# Flyback_Converter.net
KiCad netlist of a schematic drawn in Altium Designer
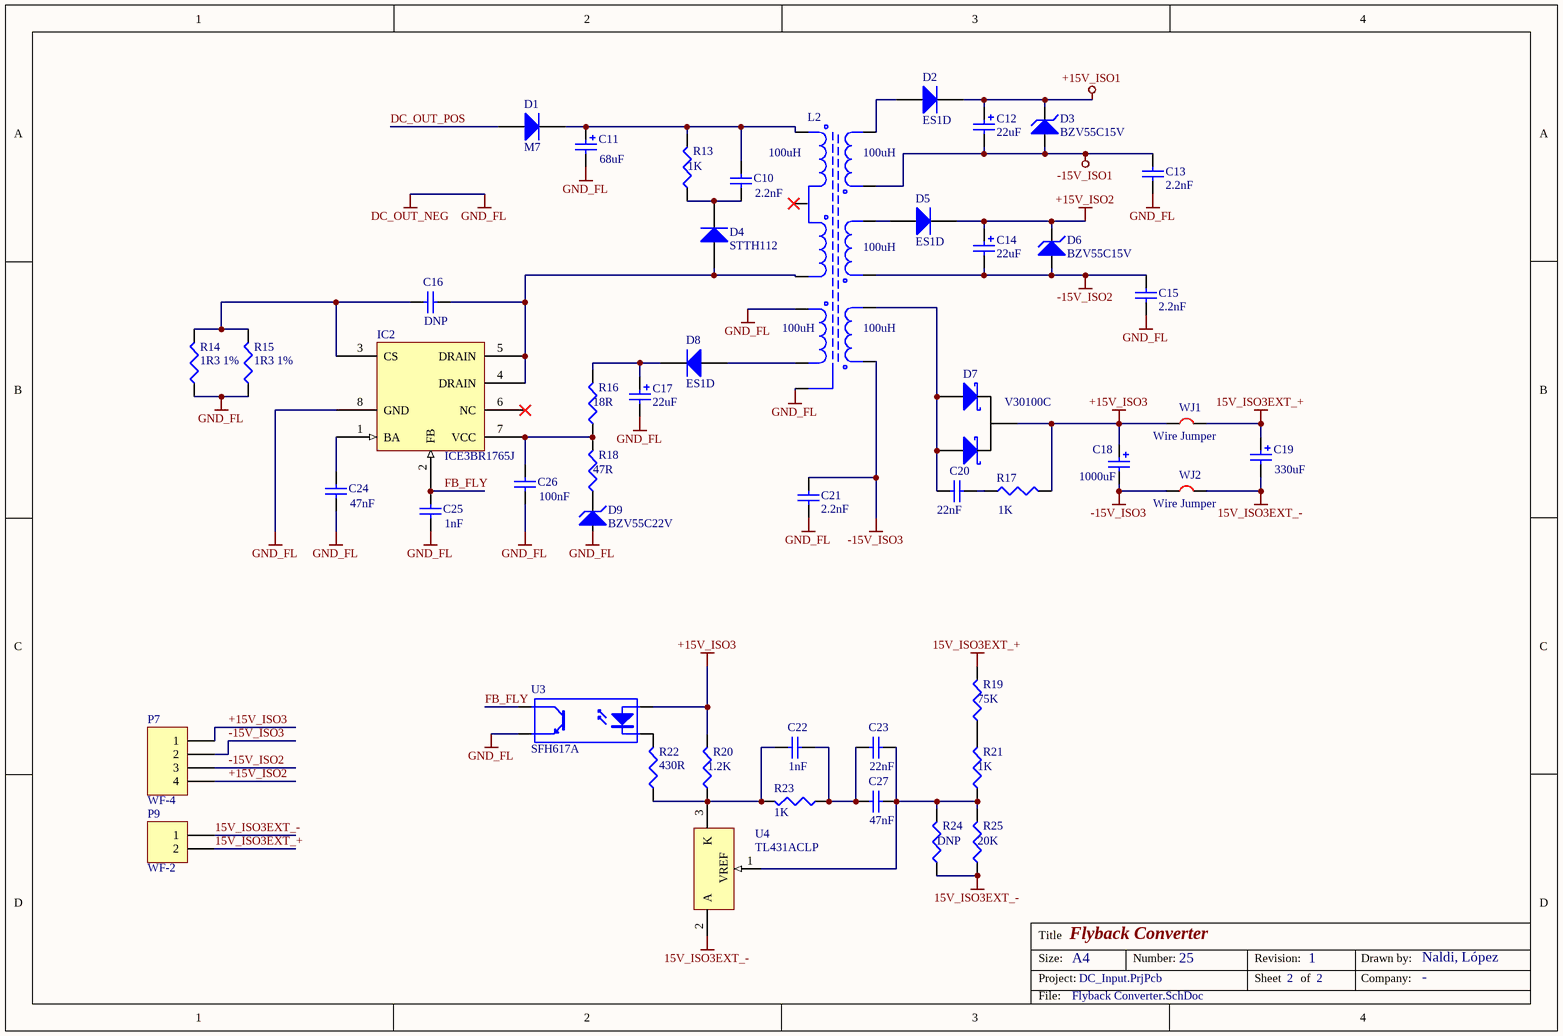
[diagram p0: Flyback Converter.SchDoc]

(export (version "E")
  (design (tool "Eeschema 10.0.6"))
  (components
    (comp (ref "C10")
      (value "2.2nF")
      (footprint "CAPC3216X18N 1206")
      (description "Ceramic Multilayer 2.2nF 630Vdc COG")
      (fields (field (name "Comment") "TDK C3216C0G2J222J115AA") (field (name "PUBLISHER") "Altium Limited"))
      (libsource (lib "Capacitor") (part "TDK C3216C0G2J222J115AA"))
    )
    (comp (ref "C11")
      (value "68uF")
      (footprint "Radial, pitch: 7.5mm diam:18mm")
      (description "MINIATURE ALUMINUM ELECTROLYTIC 68uF 400V 105ºC")
      (fields
        (field (name "Comment") "RUBYCON 400BXC68MEFC18X25")
        (field (name "PUBLISHER") "Altium Limited")
      )
      (libsource (lib "Capacitor") (part "RUBYCON 400BXC68MEFC18X25"))
    )
    (comp (ref "C12")
      (value "22uF")
      (footprint "Radial, Pitch: 2mm Diam: 5mm")
      (description "ALUMINUM ELECTROLYTIC 22UFX50V")
      (fields (field (name "Comment") "EPCOS B41827A6226M000") (field (name "PUBLISHER") "Altium Limited"))
      (libsource (lib "Capacitor") (part "EPCOS B41827A6226M000"))
    )
    (comp (ref "C13")
      (value "2.2nF")
      (footprint "SAFETY Y1 type")
      (description "Safety Standard Certified Ceramic Y1 2.2nF 250Vac")
      (fields (field (name "Comment") "TDK CD12-E2GA222MYNS") (field (name "PUBLISHER") "Altium Limited"))
      (libsource (lib "Capacitor") (part "TDK CD12-E2GA222MYNS"))
    )
    (comp (ref "C14")
      (value "22uF")
      (footprint "Radial, Pitch: 2mm Diam: 5mm")
      (description "ALUMINUM ELECTROLYTIC 22UFX50V")
      (fields (field (name "Comment") "EPCOS B41827A6226M000") (field (name "PUBLISHER") "Altium Limited"))
      (libsource (lib "Capacitor") (part "EPCOS B41827A6226M000"))
    )
    (comp (ref "C15")
      (value "2.2nF")
      (footprint "Chip2PinSM127P600-8N_safety")
      (description "Safety Standard Certified Ceramic Y2 2.2nF 250Vac")
      (fields
        (field (name "Comment") "MURATA GA355QR7GF222KW01L")
        (field (name "PUBLISHER") "Altium Limited")
      )
      (libsource (lib "Capacitor") (part "MURATA GA355QR7GF222KW01L"))
    )
    (comp (ref "C16")
      (value "DNP")
      (footprint "CAPC3216X18N 1206")
      (description "Ceramic Multilayer  50Vdc C0G")
      (fields (field (name "Comment") "EPCOS B37871K5221J60") (field (name "PUBLISHER") "Altium Limited"))
      (libsource (lib "Capacitor") (part "EPCOS B37871K5221J60"))
    )
    (comp (ref "C17")
      (value "22uF")
      (footprint "Radial, Pitch: 2mm Diam: 5mm")
      (description "ALUMINUM ELECTROLYTIC 22UFX50V")
      (fields (field (name "Comment") "EPCOS B41827A6226M000") (field (name "PUBLISHER") "Altium Limited"))
      (libsource (lib "Capacitor") (part "EPCOS B41827A6226M000"))
    )
    (comp (ref "C18")
      (value "1000uF")
      (footprint "Rad 12.5mm  pitch: 5mm")
      (description "ALuminum Electrolytic Low Impedance 105 °C 1000uF x 25V")
      (fields (field (name "Comment") "EPCOS B41856A5108M000") (field (name "PUBLISHER") "Altium Limited"))
      (libsource (lib "Capacitor") (part "EPCOS B41856A5108M000"))
    )
    (comp (ref "C19")
      (value "330uF")
      (footprint "Rad 10mm  pitch: 5mm")
      (description "ALuminum Electrolytic Low Impedance 105 °C 330uF x 25V")
      (fields (field (name "Comment") "EPCOS B41856A5337M008") (field (name "PUBLISHER") "Altium Limited"))
      (libsource (lib "Capacitor") (part "EPCOS B41856A5337M008"))
    )
    (comp (ref "C20")
      (value "22nF")
      (footprint "CAPC3216X18N 1206")
      (description "Ceramic Multilayer 22nF 50Vdc X7R")
      (fields (field (name "Comment") "EPCOS B37872K5223K60") (field (name "PUBLISHER") "Altium Limited"))
      (libsource (lib "Capacitor") (part "EPCOS B37872K5223K60"))
    )
    (comp (ref "C21")
      (value "2.2nF")
      (footprint "SAFETY Y1 type")
      (description "Safety Standard Certified Ceramic Y1 2.2nF 250Vac")
      (fields (field (name "Comment") "TDK CD12-E2GA222MYNS") (field (name "PUBLISHER") "Altium Limited"))
      (libsource (lib "Capacitor") (part "TDK CD12-E2GA222MYNS"))
    )
    (comp (ref "C22")
      (value "1nF")
      (footprint "Chip2PinSM127P600-8N")
      (description "Ceramic Multilayer 1nF 50Vdc COG")
      (fields (field (name "Comment") "EPCOS B37940K51102J60") (field (name "PUBLISHER") "Altium Limited"))
      (libsource (lib "Capacitor") (part "EPCOS B37940K51102J60"))
    )
    (comp (ref "C23")
      (value "22nF")
      (footprint "CAPC3216X18N 1206")
      (description "Ceramic Multilayer 22nF 50Vdc X7R")
      (fields (field (name "Comment") "EPCOS B37872K5223K60") (field (name "PUBLISHER") "Altium Limited"))
      (libsource (lib "Capacitor") (part "EPCOS B37872K5223K60"))
    )
    (comp (ref "C24")
      (value "47nF")
      (footprint "CAPC3216X18N 1206")
      (description "Ceramic Multilayer 47nF 50Vdc X7R")
      (fields (field (name "Comment") "EPCOS CL31B473KBCNNNC") (field (name "PUBLISHER") "Altium Limited"))
      (libsource (lib "Capacitor") (part "EPCOS CL31B473KBCNNNC"))
    )
    (comp (ref "C25")
      (value "1nF")
      (footprint "MKT Pitch: 5mm 2.5 × 7.3 mm")
      (description "MKT General purpose 1nF 63Vdc")
      (fields (field (name "Comment") "EPCOS B32529C0102K000") (field (name "PUBLISHER") "Altium Limited"))
      (libsource (lib "Capacitor") (part "EPCOS B32529C0102K000"))
    )
    (comp (ref "C26")
      (value "100nF")
      (footprint "Chip2PinSM127P600-8N")
      (description "Ceramic Multilayer 100nF 50Vdc X7R")
      (fields (field (name "Comment") "EPCOS C2012X7R1H104K") (field (name "PUBLISHER") "Altium Limited"))
      (libsource (lib "Capacitor") (part "EPCOS C2012X7R1H104K"))
    )
    (comp (ref "C27")
      (value "47nF")
      (footprint "CAPC3216X18N 1206")
      (description "Ceramic Multilayer 47nF 50Vdc X7R")
      (fields (field (name "Comment") "EPCOS CL31B473KBCNNNC") (field (name "PUBLISHER") "Altium Limited"))
      (libsource (lib "Capacitor") (part "EPCOS CL31B473KBCNNNC"))
    )
    (comp (ref "D1")
      (value "M7")
      (footprint "DIOM4326X26N - SMA")
      (description "1A 1000V SMA")
      (fields (field (name "PUBLISHER") "Altium Limited"))
      (libsource (lib "Diode") (part "M7 SMA"))
    )
    (comp (ref "D2")
      (value "ES1D")
      (footprint "DIOM4326X26N - SMA")
      (description "Ultrafast rectifier 1A 200V")
      (fields (field (name "PUBLISHER") "Altium Limited"))
      (libsource (lib "Diode") (part "ES1D"))
    )
    (comp (ref "D3")
      (value "BZV55C15V")
      (footprint "DIOMELF3515N")
      (description "Zener Diode 15V 0.5W")
      (fields (field (name "PUBLISHER") "Altium Limited"))
      (libsource (lib "Diode") (part "BZV55C15V"))
    )
    (comp (ref "D4")
      (value "STTH112")
      (footprint "DIOM4336X26N - SMB")
      (description "High voltage ultrafast rectifier")
      (fields (field (name "PUBLISHER") "Altium Limited"))
      (libsource (lib "Diode") (part "STTH112"))
    )
    (comp (ref "D5")
      (value "ES1D")
      (footprint "DIOM4326X26N - SMA")
      (description "Ultrafast rectifier 1A 200V")
      (fields (field (name "PUBLISHER") "Altium Limited"))
      (libsource (lib "Diode") (part "ES1D"))
    )
    (comp (ref "D6")
      (value "BZV55C15V")
      (footprint "DIOMELF3515N")
      (description "Zener Diode 15V 0.5W")
      (fields (field (name "PUBLISHER") "Altium Limited"))
      (libsource (lib "Diode") (part "BZV55C15V"))
    )
    (comp (ref "D7")
      (value "V30100C")
      (footprint "TO-220 Horiz. Heatsink")
      (description "Trench MOS Barrier Schottky Rectifier 2x 15A 100V")
      (libsource (lib "Diode") (part "V30100C"))
    )
    (comp (ref "D8")
      (value "ES1D")
      (footprint "DIOM4326X26N - SMA")
      (description "Ultrafast rectifier 1A 200V")
      (fields (field (name "PUBLISHER") "Altium Limited"))
      (libsource (lib "Diode") (part "ES1D"))
    )
    (comp (ref "D9")
      (value "BZV55C22V")
      (footprint "DIOMELF3515N")
      (description "Zener Diode 22V 0.5W")
      (fields (field (name "PUBLISHER") "Altium Limited"))
      (libsource (lib "Diode") (part "BZV55C22V"))
    )
    (comp (ref "IC2")
      (value "ICE3BR1765J")
      (footprint "PDIP8")
      (libsource (lib "PWM Controller") (part "ICE3BR1765J"))
    )
    (comp (ref "L2")
      (value "2 Primary, 3 Secondary, Shield")
      (footprint "CORE_E_20/10/6_14pin")
      (description "Coupled Inductors with Ferrite Core")
      (fields
        (field (name "VALUE_P1") "100uH")
        (field (name "VALUE_P2") "100uH")
        (field (name "VALUE_S1") "100uH")
        (field (name "VALUE_S2") "100uH")
        (field (name "VALUE_S3") "100uH")
        (field (name "PUBLISHER") "Altium Limited")
      )
      (libsource (lib "Inductor") (part "2 Primary, 3 Secondary, Shield"))
    )
    (comp (ref "P7")
      (value "WF-4")
      (footprint "HDR1X4")
      (description "Header, 4-Pin, 2.54mm pitch")
      (fields (field (name "PUBLISHER") "Altium Limited"))
      (libsource (lib "Connector") (part "Header 4"))
    )
    (comp (ref "P9")
      (value "WF-2")
      (footprint "HDR1X2")
      (description "Header, 2-Pin, 2.54mm pitch")
      (fields (field (name "PUBLISHER") "Altium Limited"))
      (libsource (lib "Connector") (part "Header 2"))
    )
    (comp (ref "R13")
      (value "1K")
      (footprint "Chip2PinSM127P600-8N 2512")
      (description "Resistor SMD 2512 1W")
      (fields (field (name "Comment") "Resistor SMD 2512") (field (name "PUBLISHER") "Altium Limited"))
      (libsource (lib "Resistor") (part "Resistor SMD 2512"))
    )
    (comp (ref "R14")
      (value "1R3 1%")
      (footprint "RESC3116X07N - 1206")
      (description "Resistor SMD 1206")
      (fields (field (name "PUBLISHER") "Altium Limited"))
      (libsource (lib "Resistor") (part "Resistor SMD 1206"))
    )
    (comp (ref "R15")
      (value "1R3 1%")
      (footprint "RESC3116X07N - 1206")
      (description "Resistor SMD 1206")
      (fields (field (name "PUBLISHER") "Altium Limited"))
      (libsource (lib "Resistor") (part "Resistor SMD 1206"))
    )
    (comp (ref "R16")
      (value "18R")
      (footprint "Chip2PinSM127P600-8N - 0805")
      (description "Resistor SMD 0805")
      (fields (field (name "PUBLISHER") "Altium Limited"))
      (libsource (lib "Resistor") (part "Resistor SMD 0805"))
    )
    (comp (ref "R17")
      (value "1K")
      (footprint "RESC3116X07N - 1206")
      (description "Resistor SMD 1206")
      (fields (field (name "PUBLISHER") "Altium Limited"))
      (libsource (lib "Resistor") (part "Resistor SMD 1206"))
    )
    (comp (ref "R18")
      (value "47R")
      (footprint "Chip2PinSM127P600-8N - 0805")
      (description "Resistor SMD 0805")
      (fields (field (name "PUBLISHER") "Altium Limited"))
      (libsource (lib "Resistor") (part "Resistor SMD 0805"))
    )
    (comp (ref "R19")
      (value "75K")
      (footprint "AXIAL-0.3")
      (description "Resistor 1/4W 5%")
      (fields (field (name "Comment") "Resistor Through-hole") (field (name "PUBLISHER") "Altium Limited"))
      (libsource (lib "Resistor") (part "Resistor"))
    )
    (comp (ref "R20")
      (value "1.2K")
      (footprint "Chip2PinSM127P600-8N - 0805")
      (description "Resistor SMD 0805")
      (fields (field (name "PUBLISHER") "Altium Limited"))
      (libsource (lib "Resistor") (part "Resistor SMD 0805"))
    )
    (comp (ref "R21")
      (value "1K")
      (footprint "Chip2PinSM127P600-8N - 0805")
      (description "Resistor SMD 0805")
      (fields (field (name "PUBLISHER") "Altium Limited"))
      (libsource (lib "Resistor") (part "Resistor SMD 0805"))
    )
    (comp (ref "R22")
      (value "430R")
      (footprint "Chip2PinSM127P600-8N - 0805")
      (description "Resistor SMD 0805")
      (fields (field (name "PUBLISHER") "Altium Limited"))
      (libsource (lib "Resistor") (part "Resistor SMD 0805"))
    )
    (comp (ref "R23")
      (value "1K")
      (footprint "Chip2PinSM127P600-8N - 0805")
      (description "Resistor SMD 0805")
      (fields (field (name "PUBLISHER") "Altium Limited"))
      (libsource (lib "Resistor") (part "Resistor SMD 0805"))
    )
    (comp (ref "R24")
      (value "DNP")
      (footprint "Chip2PinSM127P600-8N - 0805")
      (description "Resistor SMD 0805")
      (fields (field (name "PUBLISHER") "Altium Limited"))
      (libsource (lib "Resistor") (part "Resistor SMD 0805"))
    )
    (comp (ref "R25")
      (value "20K")
      (footprint "Chip2PinSM127P600-8N - 0805")
      (description "Resistor SMD 0805")
      (fields (field (name "PUBLISHER") "Altium Limited"))
      (libsource (lib "Resistor") (part "Resistor SMD 0805"))
    )
    (comp (ref "U3")
      (value "SFH617A")
      (footprint "DIP4")
      (description "Phototransistor Output, High Reliability,  5300 VRMS, 110 °C Rated")
      (fields (field (name "PUBLISHER") "Altium Limited"))
      (libsource (lib "Optocoupler") (part "SFH617A"))
    )
    (comp (ref "U4")
      (value "TL431ACLP")
      (footprint "LP03")
      (description "Adjustable Precision Shunt Regulator")
      (fields (field (name "PUBLISHER") "Altium Limited"))
      (libsource (lib "TI Power Mgt Voltage Regulator") (part "TL431ACLP"))
    )
    (comp (ref "WJ1") (value "Wire Jumper") (libsource (lib "SamacSys") (part "Wire Jumper")))
    (comp (ref "WJ2") (value "Wire Jumper") (libsource (lib "SamacSys") (part "Wire Jumper")))
  )
  (nets
    (net (code "1") (name "+15V_ISO1") (class "Default")
      (node (ref "C12") (pin "1") (pinfunction "1_1") (pintype "passive"))
      (node (ref "D2") (pin "1") (pinfunction "K_1") (pintype "passive"))
      (node (ref "D3") (pin "2") (pinfunction "K_2") (pintype "passive"))
    )
    (net (code "2") (name "+15V_ISO2") (class "Default")
      (node (ref "C14") (pin "1") (pinfunction "1_1") (pintype "passive"))
      (node (ref "D5") (pin "1") (pinfunction "K_1") (pintype "passive"))
      (node (ref "D6") (pin "2") (pinfunction "K_2") (pintype "passive"))
      (node (ref "P7") (pin "4") (pinfunction "4_4") (pintype "passive"))
    )
    (net (code "3") (name "+15V_ISO3") (class "Default")
      (node (ref "C18") (pin "1") (pinfunction "1_1") (pintype "passive"))
      (node (ref "D7") (pin "2") (pinfunction "K12_2") (pintype "passive"))
      (node (ref "P7") (pin "1") (pinfunction "1_1") (pintype "passive"))
      (node (ref "R17") (pin "2") (pinfunction "2_2") (pintype "passive"))
      (node (ref "R20") (pin "2") (pinfunction "2_2") (pintype "passive"))
      (node (ref "U3") (pin "1") (pinfunction "A_1") (pintype "passive"))
      (node (ref "WJ1") (pin "0") (pinfunction "0_0") (pintype "passive"))
    )
    (net (code "4") (name "-15V_ISO1") (class "Default")
      (node (ref "C12") (pin "2") (pinfunction "2_2") (pintype "passive"))
      (node (ref "C13") (pin "2") (pinfunction "2_2") (pintype "passive"))
      (node (ref "D3") (pin "1") (pinfunction "A_1") (pintype "passive"))
      (node (ref "L2") (pin "9") (pinfunction "9_9") (pintype "passive"))
    )
    (net (code "5") (name "-15V_ISO2") (class "Default")
      (node (ref "C14") (pin "2") (pinfunction "2_2") (pintype "passive"))
      (node (ref "C15") (pin "1") (pinfunction "1_1") (pintype "passive"))
      (node (ref "D6") (pin "1") (pinfunction "A_1") (pintype "passive"))
      (node (ref "L2") (pin "11") (pinfunction "11_11") (pintype "passive"))
      (node (ref "P7") (pin "3") (pinfunction "3_3") (pintype "passive"))
    )
    (net (code "6") (name "-15V_ISO3") (class "Default")
      (node (ref "C18") (pin "2") (pinfunction "2_2") (pintype "passive"))
      (node (ref "C21") (pin "2") (pinfunction "2_2") (pintype "passive"))
      (node (ref "L2") (pin "13") (pinfunction "13_13") (pintype "passive"))
      (node (ref "P7") (pin "2") (pinfunction "2_2") (pintype "passive"))
      (node (ref "WJ2") (pin "0") (pinfunction "0_0") (pintype "passive"))
    )
    (net (code "7") (name "/DC_OUT_POS") (class "Default")
      (node (ref "D1") (pin "2") (pinfunction "A_2") (pintype "passive"))
    )
    (net (code "8") (name "/FB_FLY") (class "Default")
      (node (ref "C25") (pin "2") (pinfunction "2_2") (pintype "passive"))
      (node (ref "IC2") (pin "2") (pinfunction "FB_2") (pintype "input"))
      (node (ref "U3") (pin "4") (pinfunction "C_4") (pintype "passive"))
    )
    (net (code "9") (name "15V_ISO3EXT_+") (class "Default")
      (node (ref "C19") (pin "1") (pinfunction "1_1") (pintype "passive"))
      (node (ref "P9") (pin "2") (pinfunction "2_2") (pintype "passive"))
      (node (ref "R19") (pin "2") (pinfunction "2_2") (pintype "passive"))
      (node (ref "WJ1") (pin "1") (pinfunction "1_1") (pintype "passive"))
    )
    (net (code "10") (name "15V_ISO3EXT_-") (class "Default")
      (node (ref "C19") (pin "2") (pinfunction "2_2") (pintype "passive"))
      (node (ref "P9") (pin "1") (pinfunction "1_1") (pintype "passive"))
      (node (ref "R24") (pin "1") (pinfunction "1_1") (pintype "passive"))
      (node (ref "R25") (pin "1") (pinfunction "1_1") (pintype "passive"))
      (node (ref "U4") (pin "2") (pinfunction "A_2") (pintype "power_in"))
      (node (ref "WJ2") (pin "1") (pinfunction "1_1") (pintype "passive"))
    )
    (net (code "11") (name "DC_OUT_NEG") (class "Default")
      (node (ref "C11") (pin "2") (pinfunction "2_2") (pintype "passive"))
      (node (ref "C13") (pin "1") (pinfunction "1_1") (pintype "passive"))
      (node (ref "C15") (pin "2") (pinfunction "2_2") (pintype "passive"))
      (node (ref "C17") (pin "2") (pinfunction "2_2") (pintype "passive"))
      (node (ref "C21") (pin "1") (pinfunction "1_1") (pintype "passive"))
      (node (ref "C24") (pin "1") (pinfunction "1_1") (pintype "passive"))
      (node (ref "C25") (pin "1") (pinfunction "1_1") (pintype "passive"))
      (node (ref "C26") (pin "1") (pinfunction "1_1") (pintype "passive"))
      (node (ref "D9") (pin "1") (pinfunction "A_1") (pintype "passive"))
      (node (ref "IC2") (pin "8") (pinfunction "GND_8") (pintype "power_in"))
      (node (ref "L2") (pin "1") (pinfunction "1_1") (pintype "passive"))
      (node (ref "L2") (pin "5") (pinfunction "5_5") (pintype "passive"))
      (node (ref "R14") (pin "1") (pinfunction "1_1") (pintype "passive"))
      (node (ref "R15") (pin "1") (pinfunction "1_1") (pintype "passive"))
      (node (ref "U3") (pin "3") (pinfunction "E_3") (pintype "passive"))
    )
    (net (code "12") (name "Net-(C20-Pad2)") (class "Default")
      (node (ref "C20") (pin "2") (pinfunction "2_2") (pintype "passive"))
      (node (ref "R17") (pin "1") (pinfunction "1_1") (pintype "passive"))
    )
    (net (code "13") (name "Net-(C22-Pad2)") (class "Default")
      (node (ref "C22") (pin "2") (pinfunction "2_2") (pintype "passive"))
      (node (ref "C23") (pin "1") (pinfunction "1_1") (pintype "passive"))
      (node (ref "C27") (pin "1") (pinfunction "1_1") (pintype "passive"))
      (node (ref "R23") (pin "1") (pinfunction "1_1") (pintype "passive"))
    )
    (net (code "14") (name "Net-(D1-K)") (class "Default")
      (node (ref "C10") (pin "2") (pinfunction "2_2") (pintype "passive"))
      (node (ref "C11") (pin "1") (pinfunction "1_1") (pintype "passive"))
      (node (ref "D1") (pin "1") (pinfunction "K_1") (pintype "passive"))
      (node (ref "L2") (pin "2") (pinfunction "2_2") (pintype "passive"))
      (node (ref "R13") (pin "2") (pinfunction "2_2") (pintype "passive"))
    )
    (net (code "15") (name "Net-(D2-A)") (class "Default")
      (node (ref "D2") (pin "2") (pinfunction "A_2") (pintype "passive"))
      (node (ref "L2") (pin "8") (pinfunction "8_8") (pintype "passive"))
    )
    (net (code "16") (name "Net-(D4-A)") (class "Default")
      (node (ref "C16") (pin "2") (pinfunction "2_2") (pintype "passive"))
      (node (ref "D4") (pin "2") (pinfunction "A_2") (pintype "passive"))
      (node (ref "IC2") (pin "4") (pinfunction "DRAIN_4") (pintype "open_collector"))
      (node (ref "IC2") (pin "5") (pinfunction "DRAIN_5") (pintype "open_collector"))
      (node (ref "L2") (pin "4") (pinfunction "4_4") (pintype "passive"))
    )
    (net (code "17") (name "Net-(D4-K)") (class "Default")
      (node (ref "C10") (pin "1") (pinfunction "1_1") (pintype "passive"))
      (node (ref "D4") (pin "1") (pinfunction "K_1") (pintype "passive"))
      (node (ref "R13") (pin "1") (pinfunction "1_1") (pintype "passive"))
    )
    (net (code "18") (name "Net-(D5-A)") (class "Default")
      (node (ref "D5") (pin "2") (pinfunction "A_2") (pintype "passive"))
      (node (ref "L2") (pin "10") (pinfunction "10_10") (pintype "passive"))
    )
    (net (code "19") (name "Net-(D7-A1)") (class "Default")
      (node (ref "C20") (pin "1") (pinfunction "1_1") (pintype "passive"))
      (node (ref "D7") (pin "1") (pinfunction "A1_1") (pintype "passive"))
      (node (ref "D7") (pin "3") (pinfunction "A2_3") (pintype "passive"))
      (node (ref "L2") (pin "12") (pinfunction "12_12") (pintype "passive"))
    )
    (net (code "20") (name "Net-(D8-A)") (class "Default")
      (node (ref "D8") (pin "2") (pinfunction "A_2") (pintype "passive"))
      (node (ref "L2") (pin "6") (pinfunction "6_6") (pintype "passive"))
    )
    (net (code "21") (name "Net-(D8-K)") (class "Default")
      (node (ref "C17") (pin "1") (pinfunction "1_1") (pintype "passive"))
      (node (ref "D8") (pin "1") (pinfunction "K_1") (pintype "passive"))
      (node (ref "R16") (pin "2") (pinfunction "2_2") (pintype "passive"))
    )
    (net (code "22") (name "Net-(D9-K)") (class "Default")
      (node (ref "D9") (pin "2") (pinfunction "K_2") (pintype "passive"))
      (node (ref "R18") (pin "1") (pinfunction "1_1") (pintype "passive"))
    )
    (net (code "23") (name "Net-(IC2-BA)") (class "Default")
      (node (ref "C24") (pin "2") (pinfunction "2_2") (pintype "passive"))
      (node (ref "IC2") (pin "1") (pinfunction "BA_1") (pintype "input"))
    )
    (net (code "24") (name "Net-(IC2-CS)") (class "Default")
      (node (ref "C16") (pin "1") (pinfunction "1_1") (pintype "passive"))
      (node (ref "IC2") (pin "3") (pinfunction "CS_3") (pintype "power_in"))
      (node (ref "R14") (pin "2") (pinfunction "2_2") (pintype "passive"))
      (node (ref "R15") (pin "2") (pinfunction "2_2") (pintype "passive"))
    )
    (net (code "25") (name "Net-(IC2-VCC)") (class "Default")
      (node (ref "C26") (pin "2") (pinfunction "2_2") (pintype "passive"))
      (node (ref "IC2") (pin "7") (pinfunction "VCC_7") (pintype "power_in"))
      (node (ref "R16") (pin "1") (pinfunction "1_1") (pintype "passive"))
      (node (ref "R18") (pin "2") (pinfunction "2_2") (pintype "passive"))
    )
    (net (code "26") (name "Net-(R19-Pad1)") (class "Default")
      (node (ref "R19") (pin "1") (pinfunction "1_1") (pintype "passive"))
      (node (ref "R21") (pin "2") (pinfunction "2_2") (pintype "passive"))
    )
    (net (code "27") (name "Net-(U3-K)") (class "Default")
      (node (ref "R22") (pin "2") (pinfunction "2_2") (pintype "passive"))
      (node (ref "U3") (pin "2") (pinfunction "K_2") (pintype "passive"))
    )
    (net (code "28") (name "Net-(U4-K)") (class "Default")
      (node (ref "C22") (pin "1") (pinfunction "1_1") (pintype "passive"))
      (node (ref "R20") (pin "1") (pinfunction "1_1") (pintype "passive"))
      (node (ref "R22") (pin "1") (pinfunction "1_1") (pintype "passive"))
      (node (ref "R23") (pin "2") (pinfunction "2_2") (pintype "passive"))
      (node (ref "U4") (pin "3") (pinfunction "K_3") (pintype "power_in"))
    )
    (net (code "29") (name "Net-(U4-VREF)") (class "Default")
      (node (ref "C23") (pin "2") (pinfunction "2_2") (pintype "passive"))
      (node (ref "C27") (pin "2") (pinfunction "2_2") (pintype "passive"))
      (node (ref "R21") (pin "1") (pinfunction "1_1") (pintype "passive"))
      (node (ref "R24") (pin "2") (pinfunction "2_2") (pintype "passive"))
      (node (ref "R25") (pin "2") (pinfunction "2_2") (pintype "passive"))
      (node (ref "U4") (pin "1") (pinfunction "VREF_1") (pintype "input"))
    )
    (net (code "30") (name "unconnected-(IC2-NC-Pad6)") (class "Default")
      (node (ref "IC2") (pin "6") (pinfunction "NC_6") (pintype "passive+no_connect"))
    )
    (net (code "31") (name "unconnected-(L2-Pad3)") (class "Default")
      (node (ref "L2") (pin "3") (pinfunction "3_3") (pintype "passive+no_connect"))
    )
  )
)
